# ESP8266Shield.net
KiCad netlist of a schematic drawn in EAGLE
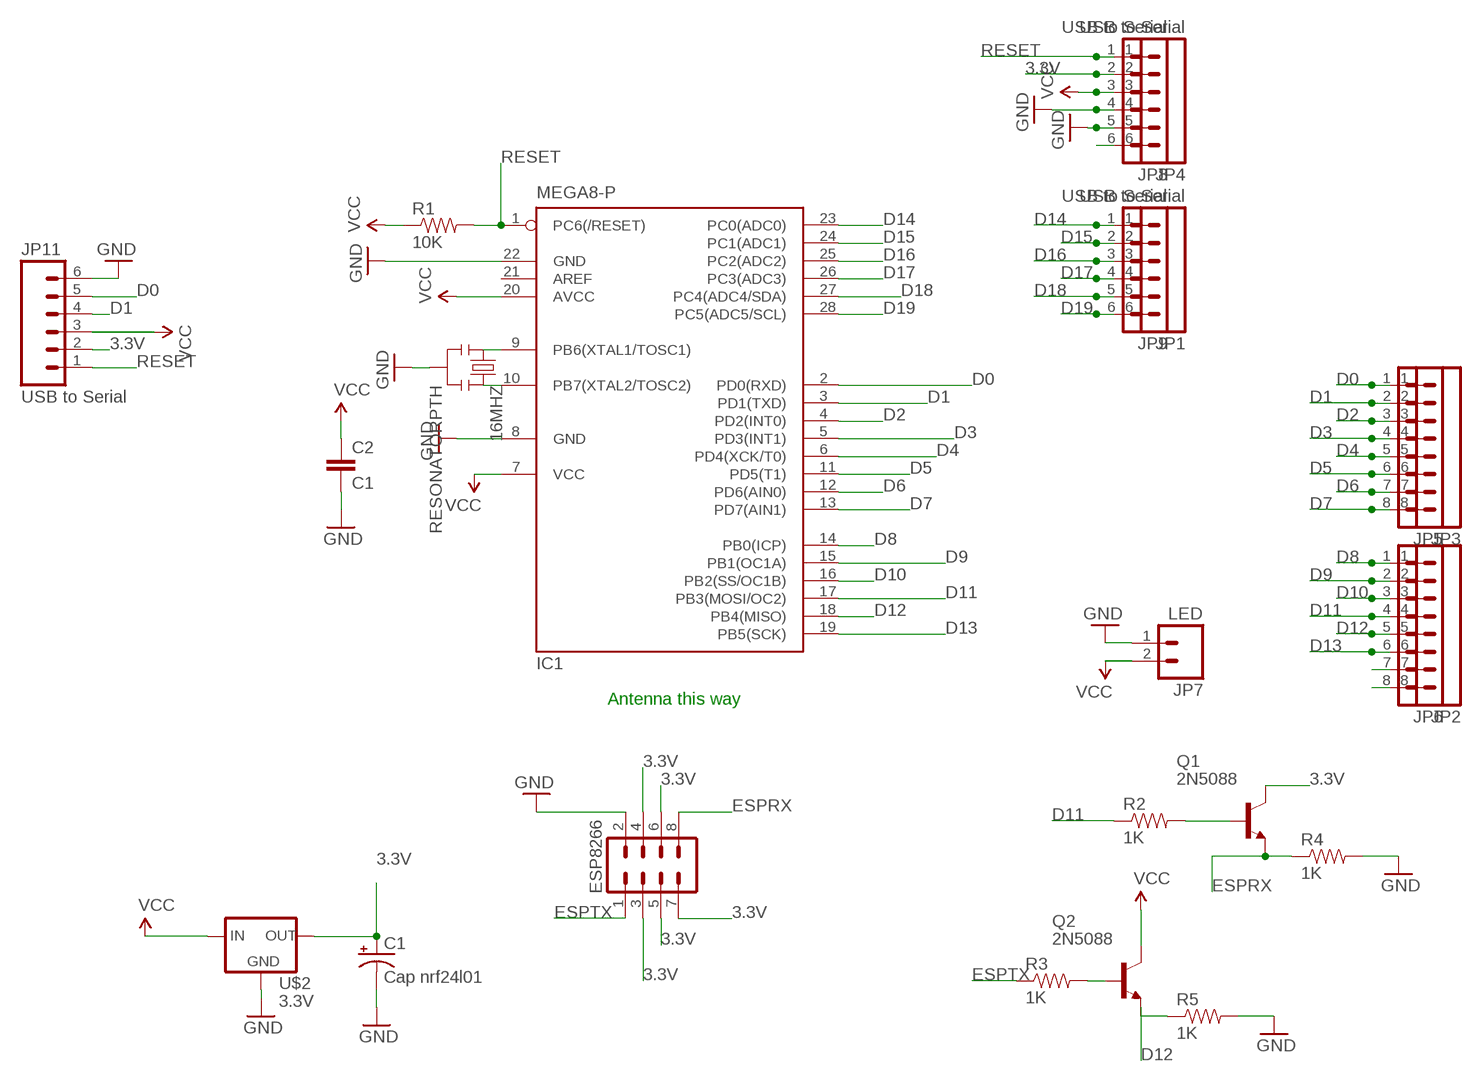
[diagram p0: schematic, sheet 1]

(export (version "E")
  (design (tool "Eeschema 10.0.6"))
  (components
    (comp (ref "16MHZ")
      (value "RESONATORPTH")
      (footprint "eagle-import:RESONATOR-PTH")
      (libsource (lib "eagle-import") (part "RESONATORPTH"))
    )
    (comp (ref "C1")
      (value "Cap nrf24l01")
      (footprint "eagle-import:CPOL-RADIAL-10UF-25V")
      (libsource (lib "eagle-import") (part "CAP_POLPTH2"))
    )
    (comp (ref "C2")
      (value "C1")
      (footprint "eagle-import:CAP-PTH-SMALL")
      (libsource (lib "eagle-import") (part "CAPPTH"))
    )
    (comp (ref "ESP8266")
      (value "M04X2")
      (footprint "eagle-import:2X4")
      (libsource (lib "eagle-import") (part "M04X2"))
    )
    (comp (ref "IC1")
      (value "MEGA8-P")
      (footprint "eagle-import:DIL28-3")
      (libsource (lib "eagle-import") (part "MEGA8-P"))
    )
    (comp (ref "JP1")
      (value "USB to Serial")
      (footprint "eagle-import:1X06")
      (libsource (lib "eagle-import") (part "M06SIP"))
    )
    (comp (ref "JP2")
      (value "M08")
      (footprint "eagle-import:1X08")
      (libsource (lib "eagle-import") (part "M08"))
    )
    (comp (ref "JP3")
      (value "M08")
      (footprint "eagle-import:1X08")
      (libsource (lib "eagle-import") (part "M08"))
    )
    (comp (ref "JP4")
      (value "USB to Serial")
      (footprint "eagle-import:1X06")
      (libsource (lib "eagle-import") (part "M06SIP"))
    )
    (comp (ref "JP5")
      (value "M08")
      (footprint "eagle-import:1X08")
      (libsource (lib "eagle-import") (part "M08"))
    )
    (comp (ref "JP6")
      (value "M08")
      (footprint "eagle-import:1X08")
      (libsource (lib "eagle-import") (part "M08"))
    )
    (comp (ref "JP7")
      (value "LED")
      (footprint "eagle-import:1X02")
      (libsource (lib "eagle-import") (part "M02PTH"))
    )
    (comp (ref "JP8")
      (value "USB to Serial")
      (footprint "eagle-import:1X06")
      (libsource (lib "eagle-import") (part "M06SIP"))
    )
    (comp (ref "JP9")
      (value "USB to Serial")
      (footprint "eagle-import:1X06")
      (libsource (lib "eagle-import") (part "M06SIP"))
    )
    (comp (ref "JP11")
      (value "USB to Serial")
      (footprint "eagle-import:1X06")
      (libsource (lib "eagle-import") (part "M06SIP"))
    )
    (comp (ref "Q1")
      (value "2N5088")
      (footprint "eagle-import:TO92")
      (libsource (lib "eagle-import") (part "2N5088"))
    )
    (comp (ref "Q2")
      (value "2N5088")
      (footprint "eagle-import:TO92")
      (libsource (lib "eagle-import") (part "2N5088"))
    )
    (comp (ref "R1")
      (value "10K")
      (footprint "eagle-import:AXIAL-0.3")
      (libsource (lib "eagle-import") (part "RESISTORPTH1"))
    )
    (comp (ref "R2")
      (value "1K")
      (footprint "eagle-import:AXIAL-0.3")
      (libsource (lib "eagle-import") (part "RESISTORPTH1"))
    )
    (comp (ref "R3")
      (value "1K")
      (footprint "eagle-import:AXIAL-0.3")
      (libsource (lib "eagle-import") (part "RESISTORPTH1"))
    )
    (comp (ref "R4")
      (value "1K")
      (footprint "eagle-import:AXIAL-0.3")
      (libsource (lib "eagle-import") (part "RESISTORPTH1"))
    )
    (comp (ref "R5")
      (value "1K")
      (footprint "eagle-import:AXIAL-0.3")
      (libsource (lib "eagle-import") (part "RESISTORPTH1"))
    )
    (comp (ref "U$2")
      (value "3.3V")
      (footprint "eagle-import:78XXL")
      (libsource (lib "eagle-import") (part "V_REG_LD1117VXX"))
    )
  )
  (nets
    (net (code "1") (name "/3.3V") (class "Default")
      (node (ref "C1") (pin "1") (pinfunction "+_1") (pintype "passive"))
      (node (ref "ESP8266") (pin "3") (pinfunction "3_3") (pintype "passive"))
      (node (ref "ESP8266") (pin "4") (pinfunction "4_4") (pintype "passive"))
      (node (ref "ESP8266") (pin "5") (pinfunction "5_5") (pintype "passive"))
      (node (ref "ESP8266") (pin "6") (pinfunction "6_6") (pintype "passive"))
      (node (ref "ESP8266") (pin "7") (pinfunction "7_7") (pintype "passive"))
      (node (ref "JP11") (pin "2") (pinfunction "2_2") (pintype "passive"))
      (node (ref "JP4") (pin "2") (pinfunction "2_2") (pintype "passive"))
      (node (ref "JP8") (pin "2") (pinfunction "2_2") (pintype "passive"))
      (node (ref "Q1") (pin "1") (pinfunction "C_1") (pintype "passive"))
      (node (ref "U$2") (pin "GND") (pinfunction "OUT_GND") (pintype "output"))
    )
    (net (code "2") (name "/D0") (class "Default")
      (node (ref "IC1") (pin "2") (pinfunction "PD0(RXD)_2") (pintype "bidirectional"))
      (node (ref "JP11") (pin "5") (pinfunction "5_5") (pintype "passive"))
      (node (ref "JP3") (pin "1") (pinfunction "1_1") (pintype "passive"))
      (node (ref "JP5") (pin "1") (pinfunction "1_1") (pintype "passive"))
      (node (ref "Q2") (pin "3") (pinfunction "E_3") (pintype "passive"))
      (node (ref "R5") (pin "P$1") (pinfunction "1_P$1") (pintype "passive"))
    )
    (net (code "3") (name "/D1") (class "Default")
      (node (ref "IC1") (pin "3") (pinfunction "PD1(TXD)_3") (pintype "bidirectional"))
      (node (ref "JP11") (pin "4") (pinfunction "4_4") (pintype "passive"))
      (node (ref "JP3") (pin "2") (pinfunction "2_2") (pintype "passive"))
      (node (ref "JP5") (pin "2") (pinfunction "2_2") (pintype "passive"))
    )
    (net (code "4") (name "/D2") (class "Default")
      (node (ref "IC1") (pin "4") (pinfunction "PD2(INT0)_4") (pintype "bidirectional"))
      (node (ref "JP3") (pin "3") (pinfunction "3_3") (pintype "passive"))
      (node (ref "JP5") (pin "3") (pinfunction "3_3") (pintype "passive"))
    )
    (net (code "5") (name "/D3") (class "Default")
      (node (ref "IC1") (pin "5") (pinfunction "PD3(INT1)_5") (pintype "bidirectional"))
      (node (ref "JP3") (pin "4") (pinfunction "4_4") (pintype "passive"))
      (node (ref "JP5") (pin "4") (pinfunction "4_4") (pintype "passive"))
    )
    (net (code "6") (name "/D4") (class "Default")
      (node (ref "IC1") (pin "6") (pinfunction "PD4(XCK/T0)_6") (pintype "bidirectional"))
      (node (ref "JP3") (pin "5") (pinfunction "5_5") (pintype "passive"))
      (node (ref "JP5") (pin "5") (pinfunction "5_5") (pintype "passive"))
    )
    (net (code "7") (name "/D5") (class "Default")
      (node (ref "IC1") (pin "11") (pinfunction "PD5(T1)_11") (pintype "bidirectional"))
      (node (ref "JP3") (pin "6") (pinfunction "6_6") (pintype "passive"))
      (node (ref "JP5") (pin "6") (pinfunction "6_6") (pintype "passive"))
    )
    (net (code "8") (name "/D6") (class "Default")
      (node (ref "IC1") (pin "12") (pinfunction "PD6(AIN0)_12") (pintype "bidirectional"))
      (node (ref "JP3") (pin "7") (pinfunction "7_7") (pintype "passive"))
      (node (ref "JP5") (pin "7") (pinfunction "7_7") (pintype "passive"))
    )
    (net (code "9") (name "/D7") (class "Default")
      (node (ref "IC1") (pin "13") (pinfunction "PD7(AIN1)_13") (pintype "bidirectional"))
      (node (ref "JP3") (pin "8") (pinfunction "8_8") (pintype "passive"))
      (node (ref "JP5") (pin "8") (pinfunction "8_8") (pintype "passive"))
    )
    (net (code "10") (name "/D8") (class "Default")
      (node (ref "IC1") (pin "14") (pinfunction "PB0(ICP)_14") (pintype "bidirectional"))
      (node (ref "JP2") (pin "1") (pinfunction "1_1") (pintype "passive"))
      (node (ref "JP6") (pin "1") (pinfunction "1_1") (pintype "passive"))
    )
    (net (code "11") (name "/D9") (class "Default")
      (node (ref "IC1") (pin "15") (pinfunction "PB1(OC1A)_15") (pintype "bidirectional"))
      (node (ref "JP2") (pin "2") (pinfunction "2_2") (pintype "passive"))
      (node (ref "JP6") (pin "2") (pinfunction "2_2") (pintype "passive"))
    )
    (net (code "12") (name "/D10") (class "Default")
      (node (ref "IC1") (pin "16") (pinfunction "PB2(SS/OC1B)_16") (pintype "bidirectional"))
      (node (ref "JP2") (pin "3") (pinfunction "3_3") (pintype "passive"))
      (node (ref "JP6") (pin "3") (pinfunction "3_3") (pintype "passive"))
    )
    (net (code "13") (name "/D11") (class "Default")
      (node (ref "IC1") (pin "17") (pinfunction "PB3(MOSI/OC2)_17") (pintype "bidirectional"))
      (node (ref "JP2") (pin "4") (pinfunction "4_4") (pintype "passive"))
      (node (ref "JP6") (pin "4") (pinfunction "4_4") (pintype "passive"))
      (node (ref "R2") (pin "P$1") (pinfunction "1_P$1") (pintype "passive"))
    )
    (net (code "14") (name "/D12") (class "Default")
      (node (ref "IC1") (pin "18") (pinfunction "PB4(MISO)_18") (pintype "bidirectional"))
      (node (ref "JP2") (pin "5") (pinfunction "5_5") (pintype "passive"))
      (node (ref "JP6") (pin "5") (pinfunction "5_5") (pintype "passive"))
    )
    (net (code "15") (name "/D13") (class "Default")
      (node (ref "IC1") (pin "19") (pinfunction "PB5(SCK)_19") (pintype "bidirectional"))
      (node (ref "JP2") (pin "6") (pinfunction "6_6") (pintype "passive"))
      (node (ref "JP6") (pin "6") (pinfunction "6_6") (pintype "passive"))
    )
    (net (code "16") (name "/D14") (class "Default")
      (node (ref "IC1") (pin "23") (pinfunction "PC0(ADC0)_23") (pintype "bidirectional"))
      (node (ref "JP1") (pin "1") (pinfunction "1_1") (pintype "passive"))
      (node (ref "JP9") (pin "1") (pinfunction "1_1") (pintype "passive"))
    )
    (net (code "17") (name "/D15") (class "Default")
      (node (ref "IC1") (pin "24") (pinfunction "PC1(ADC1)_24") (pintype "bidirectional"))
      (node (ref "JP1") (pin "2") (pinfunction "2_2") (pintype "passive"))
      (node (ref "JP9") (pin "2") (pinfunction "2_2") (pintype "passive"))
    )
    (net (code "18") (name "/D16") (class "Default")
      (node (ref "IC1") (pin "25") (pinfunction "PC2(ADC2)_25") (pintype "bidirectional"))
      (node (ref "JP1") (pin "3") (pinfunction "3_3") (pintype "passive"))
      (node (ref "JP9") (pin "3") (pinfunction "3_3") (pintype "passive"))
    )
    (net (code "19") (name "/D17") (class "Default")
      (node (ref "IC1") (pin "26") (pinfunction "PC3(ADC3)_26") (pintype "bidirectional"))
      (node (ref "JP1") (pin "4") (pinfunction "4_4") (pintype "passive"))
      (node (ref "JP9") (pin "4") (pinfunction "4_4") (pintype "passive"))
    )
    (net (code "20") (name "/D18") (class "Default")
      (node (ref "IC1") (pin "27") (pinfunction "PC4(ADC4/SDA)_27") (pintype "bidirectional"))
      (node (ref "JP1") (pin "5") (pinfunction "5_5") (pintype "passive"))
      (node (ref "JP9") (pin "5") (pinfunction "5_5") (pintype "passive"))
    )
    (net (code "21") (name "/D19") (class "Default")
      (node (ref "IC1") (pin "28") (pinfunction "PC5(ADC5/SCL)_28") (pintype "bidirectional"))
      (node (ref "JP1") (pin "6") (pinfunction "6_6") (pintype "passive"))
      (node (ref "JP9") (pin "6") (pinfunction "6_6") (pintype "passive"))
    )
    (net (code "22") (name "/ESPRX") (class "Default")
      (node (ref "ESP8266") (pin "8") (pinfunction "8_8") (pintype "passive"))
      (node (ref "Q1") (pin "3") (pinfunction "E_3") (pintype "passive"))
      (node (ref "R4") (pin "P$1") (pinfunction "1_P$1") (pintype "passive"))
    )
    (net (code "23") (name "/ESPTX") (class "Default")
      (node (ref "ESP8266") (pin "1") (pinfunction "1_1") (pintype "passive"))
      (node (ref "R3") (pin "P$1") (pinfunction "1_P$1") (pintype "passive"))
    )
    (net (code "24") (name "/RESET") (class "Default")
      (node (ref "IC1") (pin "1") (pinfunction "PC6(/RESET)_1") (pintype "bidirectional"))
      (node (ref "JP11") (pin "1") (pinfunction "1_1") (pintype "passive"))
      (node (ref "JP4") (pin "1") (pinfunction "1_1") (pintype "passive"))
      (node (ref "JP8") (pin "1") (pinfunction "1_1") (pintype "passive"))
      (node (ref "R1") (pin "P$2") (pinfunction "2_P$2") (pintype "passive"))
    )
    (net (code "25") (name "GND") (class "Default")
      (node (ref "16MHZ") (pin "2") (pinfunction "2_2") (pintype "passive"))
      (node (ref "C1") (pin "2") (pinfunction "-_2") (pintype "passive"))
      (node (ref "C2") (pin "2") (pinfunction "2_2") (pintype "passive"))
      (node (ref "ESP8266") (pin "2") (pinfunction "2_2") (pintype "passive"))
      (node (ref "IC1") (pin "22") (pinfunction "GND_22") (pintype "power_in"))
      (node (ref "IC1") (pin "8") (pinfunction "GND_8") (pintype "power_in"))
      (node (ref "JP11") (pin "6") (pinfunction "6_6") (pintype "passive"))
      (node (ref "JP4") (pin "4") (pinfunction "4_4") (pintype "passive"))
      (node (ref "JP4") (pin "5") (pinfunction "5_5") (pintype "passive"))
      (node (ref "JP7") (pin "1") (pinfunction "1_1") (pintype "passive"))
      (node (ref "JP8") (pin "4") (pinfunction "4_4") (pintype "passive"))
      (node (ref "JP8") (pin "5") (pinfunction "5_5") (pintype "passive"))
      (node (ref "R4") (pin "P$2") (pinfunction "2_P$2") (pintype "passive"))
      (node (ref "R5") (pin "P$2") (pinfunction "2_P$2") (pintype "passive"))
      (node (ref "U$2") (pin "IN") (pinfunction "GND_IN") (pintype "input"))
    )
    (net (code "26") (name "Net-(IC1-PB6(XTAL1{slash}TOSC1))") (class "Default")
      (node (ref "16MHZ") (pin "1") (pinfunction "1_1") (pintype "passive"))
      (node (ref "IC1") (pin "9") (pinfunction "PB6(XTAL1/TOSC1)_9") (pintype "bidirectional"))
    )
    (net (code "27") (name "Net-(IC1-PB7(XTAL2{slash}TOSC2))") (class "Default")
      (node (ref "16MHZ") (pin "3") (pinfunction "3_3") (pintype "passive"))
      (node (ref "IC1") (pin "10") (pinfunction "PB7(XTAL2/TOSC2)_10") (pintype "bidirectional"))
    )
    (net (code "28") (name "Net-(JP2-Pad7)") (class "Default")
      (node (ref "JP2") (pin "7") (pinfunction "7_7") (pintype "passive"))
      (node (ref "JP6") (pin "7") (pinfunction "7_7") (pintype "passive"))
    )
    (net (code "29") (name "Net-(JP2-Pad8)") (class "Default")
      (node (ref "JP2") (pin "8") (pinfunction "8_8") (pintype "passive"))
      (node (ref "JP6") (pin "8") (pinfunction "8_8") (pintype "passive"))
    )
    (net (code "30") (name "Net-(JP4-Pad6)") (class "Default")
      (node (ref "JP4") (pin "6") (pinfunction "6_6") (pintype "passive"))
      (node (ref "JP8") (pin "6") (pinfunction "6_6") (pintype "passive"))
    )
    (net (code "31") (name "Net-(Q1-B)") (class "Default")
      (node (ref "Q1") (pin "2") (pinfunction "B_2") (pintype "passive"))
      (node (ref "R2") (pin "P$2") (pinfunction "2_P$2") (pintype "passive"))
    )
    (net (code "32") (name "Net-(Q2-B)") (class "Default")
      (node (ref "Q2") (pin "2") (pinfunction "B_2") (pintype "passive"))
      (node (ref "R3") (pin "P$2") (pinfunction "2_P$2") (pintype "passive"))
    )
    (net (code "33") (name "VCC") (class "Default")
      (node (ref "C2") (pin "1") (pinfunction "1_1") (pintype "passive"))
      (node (ref "IC1") (pin "20") (pinfunction "AVCC_20") (pintype "power_in"))
      (node (ref "IC1") (pin "7") (pinfunction "VCC_7") (pintype "power_in"))
      (node (ref "JP11") (pin "3") (pinfunction "3_3") (pintype "passive"))
      (node (ref "JP4") (pin "3") (pinfunction "3_3") (pintype "passive"))
      (node (ref "JP7") (pin "2") (pinfunction "2_2") (pintype "passive"))
      (node (ref "JP8") (pin "3") (pinfunction "3_3") (pintype "passive"))
      (node (ref "Q2") (pin "1") (pinfunction "C_1") (pintype "passive"))
      (node (ref "R1") (pin "P$1") (pinfunction "1_P$1") (pintype "passive"))
      (node (ref "U$2") (pin "OUT") (pinfunction "IN_OUT") (pintype "input"))
    )
    (net (code "34") (name "unconnected-(IC1-AREF-Pad21)") (class "Default")
      (node (ref "IC1") (pin "21") (pinfunction "AREF_21") (pintype "passive"))
    )
  )
)
